# OPV_Psu.net
KiCad netlist of a schematic drawn in Altium Designer
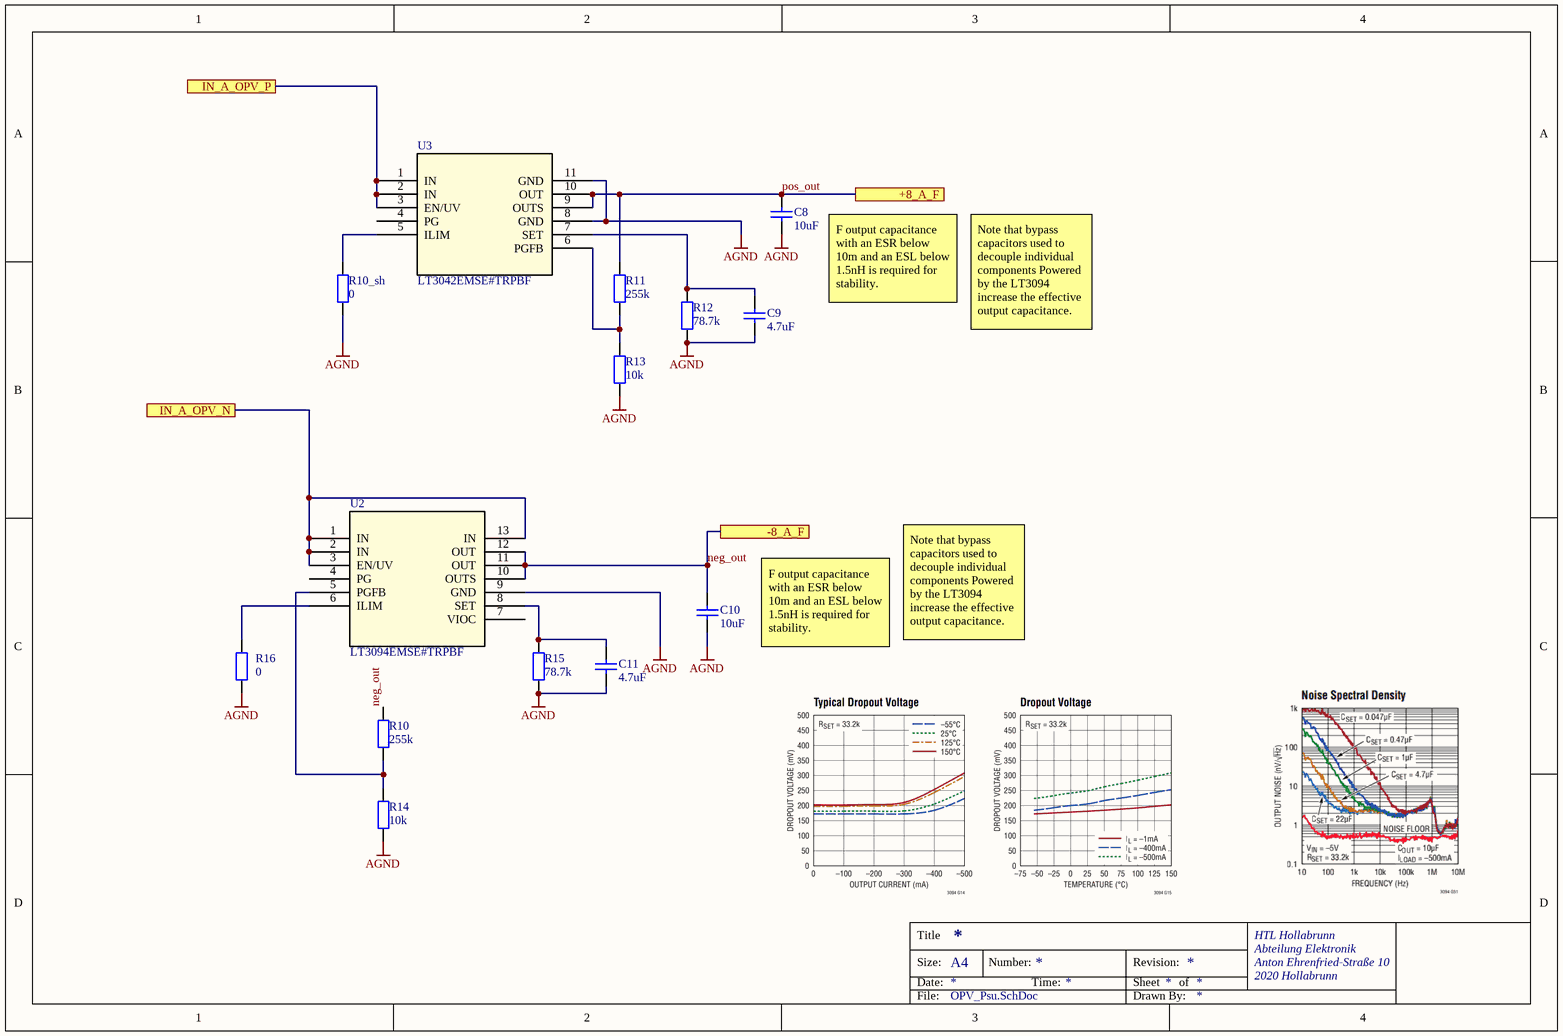
[diagram p0: OPV_Psu.SchDoc]

(export (version "E")
  (design (tool "Eeschema 10.0.6"))
  (components
    (comp (ref "C8")
      (value "10uF")
      (footprint "C1206-KUE")
      (description "Capacitor")
      (fields (field (name "MANUFACTURER") "Kemet") (field (name "PUBLISHER") "Altium Limited"))
      (libsource (lib "ExtrapartsKUE_V01") (part "Capacitor"))
    )
    (comp (ref "C9")
      (value "4.7uF")
      (footprint "C1206-KUE")
      (description "Capacitor")
      (fields (field (name "MANUFACTURER") "Kemet") (field (name "PUBLISHER") "Altium Limited"))
      (libsource (lib "ExtrapartsKUE_V01") (part "Capacitor"))
    )
    (comp (ref "C10")
      (value "10uF")
      (footprint "C1206-KUE")
      (description "Capacitor")
      (fields (field (name "MANUFACTURER") "Kemet") (field (name "PUBLISHER") "Altium Limited"))
      (libsource (lib "ExtrapartsKUE_V01") (part "Capacitor"))
    )
    (comp (ref "C11")
      (value "4.7uF")
      (footprint "C1206-KUE")
      (description "Capacitor")
      (fields (field (name "MANUFACTURER") "Kemet") (field (name "PUBLISHER") "Altium Limited"))
      (libsource (lib "ExtrapartsKUE_V01") (part "Capacitor"))
    )
    (comp (ref "R10")
      (value "255k")
      (footprint "C1206-KUE")
      (description "Resistor SMD")
      (fields (field (name "MANUFACTURER") "AVX") (field (name "PUBLISHER") "Altium Limited"))
      (libsource (lib "ExtrapartsKUE_V01") (part "ResistorSMD"))
    )
    (comp (ref "R10_sh")
      (value "0")
      (footprint "C1206-KUE")
      (description "Resistor SMD")
      (fields (field (name "MANUFACTURER") "AVX") (field (name "PUBLISHER") "Altium Limited"))
      (libsource (lib "ExtrapartsKUE_V01") (part "ResistorSMD"))
    )
    (comp (ref "R11")
      (value "255k")
      (footprint "C1206-KUE")
      (description "Resistor SMD")
      (fields (field (name "MANUFACTURER") "AVX") (field (name "PUBLISHER") "Altium Limited"))
      (libsource (lib "ExtrapartsKUE_V01") (part "ResistorSMD"))
    )
    (comp (ref "R12")
      (value "78.7k")
      (footprint "C1206-KUE")
      (description "Resistor SMD")
      (fields (field (name "MANUFACTURER") "AVX") (field (name "PUBLISHER") "Altium Limited"))
      (libsource (lib "ExtrapartsKUE_V01") (part "ResistorSMD"))
    )
    (comp (ref "R13")
      (value "10k")
      (footprint "C1206-KUE")
      (description "Resistor SMD")
      (fields (field (name "MANUFACTURER") "AVX") (field (name "PUBLISHER") "Altium Limited"))
      (libsource (lib "ExtrapartsKUE_V01") (part "ResistorSMD"))
    )
    (comp (ref "R14")
      (value "10k")
      (footprint "C1206-KUE")
      (description "Resistor SMD")
      (fields (field (name "MANUFACTURER") "AVX") (field (name "PUBLISHER") "Altium Limited"))
      (libsource (lib "ExtrapartsKUE_V01") (part "ResistorSMD"))
    )
    (comp (ref "R15")
      (value "78.7k")
      (footprint "C1206-KUE")
      (description "Resistor SMD")
      (fields (field (name "MANUFACTURER") "AVX") (field (name "PUBLISHER") "Altium Limited"))
      (libsource (lib "ExtrapartsKUE_V01") (part "ResistorSMD"))
    )
    (comp (ref "R16")
      (value "0")
      (footprint "C1206-KUE")
      (description "Resistor SMD")
      (fields (field (name "MANUFACTURER") "AVX") (field (name "PUBLISHER") "Altium Limited"))
      (libsource (lib "ExtrapartsKUE_V01") (part "ResistorSMD"))
    )
    (comp (ref "U2")
      (value "LT3094EMSE#TRPBF")
      (footprint "MSE_05-08-1666_ADI")
      (description "âˆ’20V, 500mA, Ultralow Noise, Ultrahigh PSRR Negative Linear Regulator")
      (fields (field (name "COPYRIGHT") "Copyright (C) 2025 Ultra Librarian. All rights reserved."))
      (libsource (lib "MyOwnParts") (part "LT3094EMSETRPBF"))
    )
    (comp (ref "U3")
      (value "LT3042EMSE#TRPBF")
      (footprint "05-08-1664_ADI")
      (description "20V, 200mA, Ultralow Noise, Ultrahigh PSRR RF Linear Regulator")
      (fields (field (name "COPYRIGHT") "Copyright (C) 2025 Ultra Librarian. All rights reserved."))
      (libsource (lib "MyOwnParts") (part "LT3042EMSETRPBF"))
    )
  )
  (nets
    (net (code "1") (name "/IN_A_OPV_N") (class "Default")
      (node (ref "U2") (pin "1") (pinfunction "IN_1") (pintype "passive"))
      (node (ref "U2") (pin "13") (pinfunction "IN_13") (pintype "passive"))
      (node (ref "U2") (pin "2") (pinfunction "IN_2") (pintype "passive"))
      (node (ref "U2") (pin "3") (pinfunction "EN/UV_3") (pintype "passive"))
    )
    (net (code "2") (name "/IN_A_OPV_P") (class "Default")
      (node (ref "U3") (pin "1") (pinfunction "IN_1") (pintype "power_in"))
      (node (ref "U3") (pin "2") (pinfunction "IN_2") (pintype "power_in"))
      (node (ref "U3") (pin "3") (pinfunction "EN/UV_3") (pintype "passive"))
    )
    (net (code "3") (name "/neg_out") (class "Default")
      (node (ref "C10") (pin "2") (pinfunction "2_2") (pintype "passive"))
      (node (ref "R10") (pin "1") (pinfunction "1_1") (pintype "passive"))
      (node (ref "U2") (pin "10") (pinfunction "OUTS_10") (pintype "passive"))
      (node (ref "U2") (pin "11") (pinfunction "OUT_11") (pintype "passive"))
      (node (ref "U2") (pin "12") (pinfunction "OUT_12") (pintype "passive"))
    )
    (net (code "4") (name "/pos_out") (class "Default")
      (node (ref "C8") (pin "2") (pinfunction "2_2") (pintype "passive"))
      (node (ref "R11") (pin "1") (pinfunction "1_1") (pintype "passive"))
      (node (ref "U3") (pin "10") (pinfunction "OUT_10") (pintype "passive"))
      (node (ref "U3") (pin "9") (pinfunction "OUTS_9") (pintype "passive"))
    )
    (net (code "5") (name "AGND") (class "Default")
      (node (ref "C10") (pin "1") (pinfunction "1_1") (pintype "passive"))
      (node (ref "C11") (pin "1") (pinfunction "1_1") (pintype "passive"))
      (node (ref "C8") (pin "1") (pinfunction "1_1") (pintype "passive"))
      (node (ref "C9") (pin "1") (pinfunction "1_1") (pintype "passive"))
      (node (ref "R10_sh") (pin "2") (pinfunction "2_2") (pintype "passive"))
      (node (ref "R12") (pin "2") (pinfunction "2_2") (pintype "passive"))
      (node (ref "R13") (pin "2") (pinfunction "2_2") (pintype "passive"))
      (node (ref "R14") (pin "2") (pinfunction "2_2") (pintype "passive"))
      (node (ref "R15") (pin "2") (pinfunction "2_2") (pintype "passive"))
      (node (ref "R16") (pin "2") (pinfunction "2_2") (pintype "passive"))
      (node (ref "U2") (pin "9") (pinfunction "GND_9") (pintype "passive"))
      (node (ref "U3") (pin "11") (pinfunction "GND_11") (pintype "power_in"))
      (node (ref "U3") (pin "8") (pinfunction "GND_8") (pintype "power_in"))
    )
    (net (code "6") (name "Net-(U2-ILIM)") (class "Default")
      (node (ref "R16") (pin "1") (pinfunction "1_1") (pintype "passive"))
      (node (ref "U2") (pin "6") (pinfunction "ILIM_6") (pintype "passive"))
    )
    (net (code "7") (name "Net-(U2-PGFB)") (class "Default")
      (node (ref "R10") (pin "2") (pinfunction "2_2") (pintype "passive"))
      (node (ref "R14") (pin "1") (pinfunction "1_1") (pintype "passive"))
      (node (ref "U2") (pin "5") (pinfunction "PGFB_5") (pintype "passive"))
    )
    (net (code "8") (name "Net-(U2-SET)") (class "Default")
      (node (ref "C11") (pin "2") (pinfunction "2_2") (pintype "passive"))
      (node (ref "R15") (pin "1") (pinfunction "1_1") (pintype "passive"))
      (node (ref "U2") (pin "8") (pinfunction "SET_8") (pintype "passive"))
    )
    (net (code "9") (name "Net-(U3-ILIM)") (class "Default")
      (node (ref "R10_sh") (pin "1") (pinfunction "1_1") (pintype "passive"))
      (node (ref "U3") (pin "5") (pinfunction "ILIM_5") (pintype "passive"))
    )
    (net (code "10") (name "Net-(U3-PGFB)") (class "Default")
      (node (ref "R11") (pin "2") (pinfunction "2_2") (pintype "passive"))
      (node (ref "R13") (pin "1") (pinfunction "1_1") (pintype "passive"))
      (node (ref "U3") (pin "6") (pinfunction "PGFB_6") (pintype "passive"))
    )
    (net (code "11") (name "Net-(U3-SET)") (class "Default")
      (node (ref "C9") (pin "2") (pinfunction "2_2") (pintype "passive"))
      (node (ref "R12") (pin "1") (pinfunction "1_1") (pintype "passive"))
      (node (ref "U3") (pin "7") (pinfunction "SET_7") (pintype "passive"))
    )
    (net (code "12") (name "unconnected-(U2-PG-Pad4)") (class "Default")
      (node (ref "U2") (pin "4") (pinfunction "PG_4") (pintype "passive"))
    )
    (net (code "13") (name "unconnected-(U2-VIOC-Pad7)") (class "Default")
      (node (ref "U2") (pin "7") (pinfunction "VIOC_7") (pintype "passive"))
    )
    (net (code "14") (name "unconnected-(U3-PG-Pad4)") (class "Default")
      (node (ref "U3") (pin "4") (pinfunction "PG_4") (pintype "passive"))
    )
  )
)
